# megatemp.net
KiCad netlist of a schematic drawn in EAGLE
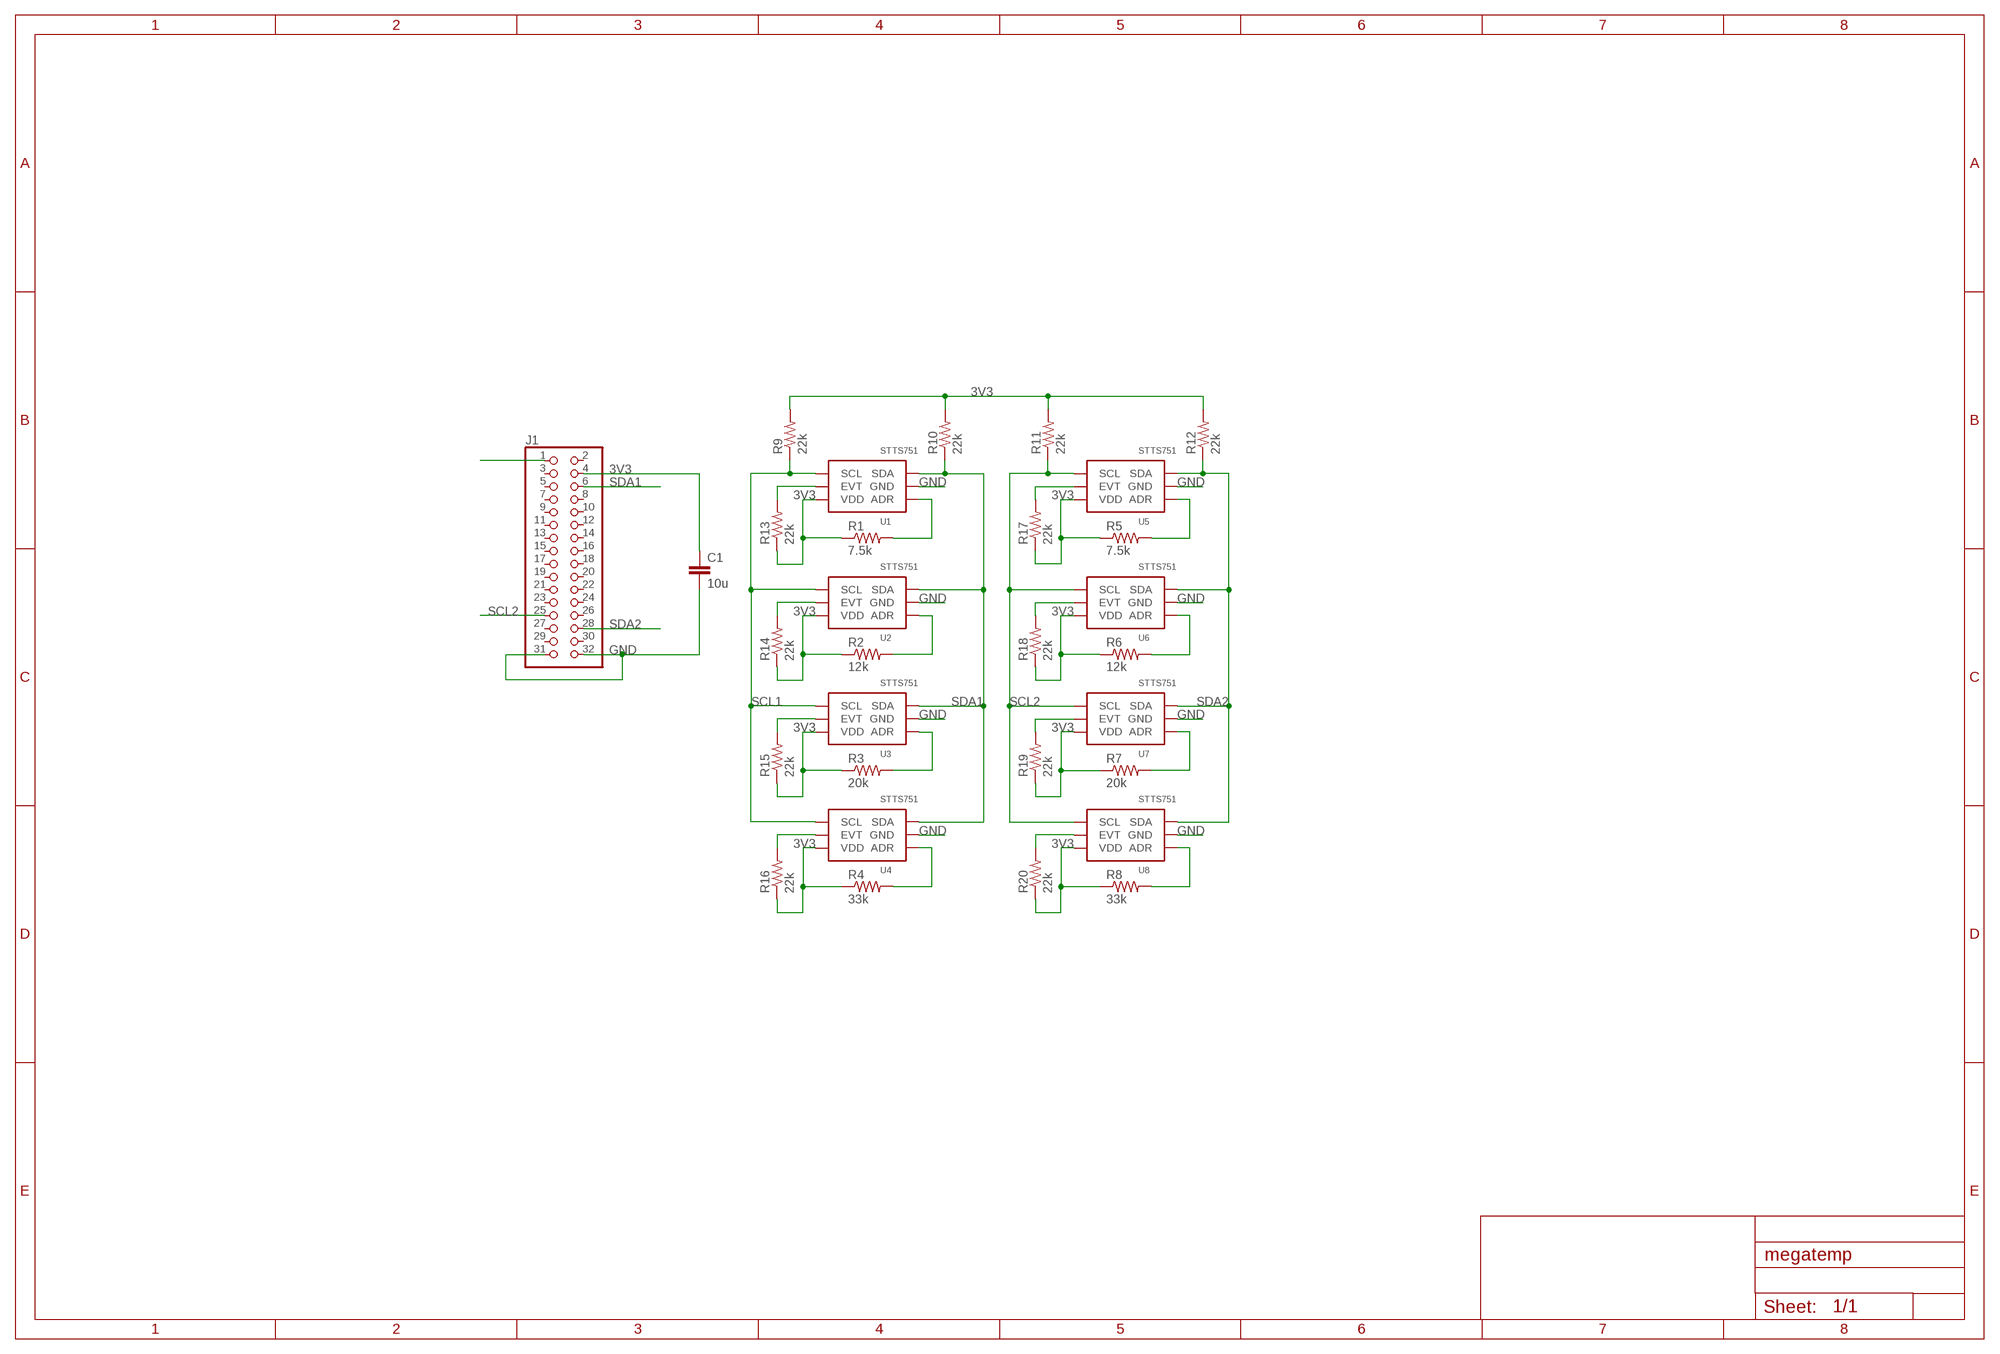
[diagram p0: schematic, sheet 1]

(export (version "E")
  (design (tool "Eeschema 10.0.6"))
  (components
    (comp (ref "C1")
      (value "10u")
      (footprint "eagle-import:C0805")
      (libsource (lib "eagle-import") (part "C-EUC0805"))
    )
    (comp (ref "J1")
      (value "PINHD-2X16")
      (footprint "eagle-import:2X16")
      (libsource (lib "eagle-import") (part "PINHD-2X16"))
    )
    (comp (ref "R1")
      (value "7.5k")
      (footprint "eagle-import:R0402")
      (libsource (lib "eagle-import") (part "R-US_R0402"))
    )
    (comp (ref "R2")
      (value "12k")
      (footprint "eagle-import:R0402")
      (libsource (lib "eagle-import") (part "R-US_R0402"))
    )
    (comp (ref "R3")
      (value "20k")
      (footprint "eagle-import:R0402")
      (libsource (lib "eagle-import") (part "R-US_R0402"))
    )
    (comp (ref "R4")
      (value "33k")
      (footprint "eagle-import:R0402")
      (libsource (lib "eagle-import") (part "R-US_R0402"))
    )
    (comp (ref "R5")
      (value "7.5k")
      (footprint "eagle-import:R0402")
      (libsource (lib "eagle-import") (part "R-US_R0402"))
    )
    (comp (ref "R6")
      (value "12k")
      (footprint "eagle-import:R0402")
      (libsource (lib "eagle-import") (part "R-US_R0402"))
    )
    (comp (ref "R7")
      (value "20k")
      (footprint "eagle-import:R0402")
      (libsource (lib "eagle-import") (part "R-US_R0402"))
    )
    (comp (ref "R8")
      (value "33k")
      (footprint "eagle-import:R0402")
      (libsource (lib "eagle-import") (part "R-US_R0402"))
    )
    (comp (ref "R9")
      (value "22k")
      (footprint "eagle-import:R0402")
      (libsource (lib "eagle-import") (part "R-US_R0402"))
    )
    (comp (ref "R10")
      (value "22k")
      (footprint "eagle-import:R0402")
      (libsource (lib "eagle-import") (part "R-US_R0402"))
    )
    (comp (ref "R11")
      (value "22k")
      (footprint "eagle-import:R0402")
      (libsource (lib "eagle-import") (part "R-US_R0402"))
    )
    (comp (ref "R12")
      (value "22k")
      (footprint "eagle-import:R0402")
      (libsource (lib "eagle-import") (part "R-US_R0402"))
    )
    (comp (ref "R13")
      (value "22k")
      (footprint "eagle-import:R0402")
      (libsource (lib "eagle-import") (part "R-US_R0402"))
    )
    (comp (ref "R14")
      (value "22k")
      (footprint "eagle-import:R0402")
      (libsource (lib "eagle-import") (part "R-US_R0402"))
    )
    (comp (ref "R15")
      (value "22k")
      (footprint "eagle-import:R0402")
      (libsource (lib "eagle-import") (part "R-US_R0402"))
    )
    (comp (ref "R16")
      (value "22k")
      (footprint "eagle-import:R0402")
      (libsource (lib "eagle-import") (part "R-US_R0402"))
    )
    (comp (ref "R17")
      (value "22k")
      (footprint "eagle-import:R0402")
      (libsource (lib "eagle-import") (part "R-US_R0402"))
    )
    (comp (ref "R18")
      (value "22k")
      (footprint "eagle-import:R0402")
      (libsource (lib "eagle-import") (part "R-US_R0402"))
    )
    (comp (ref "R19")
      (value "22k")
      (footprint "eagle-import:R0402")
      (libsource (lib "eagle-import") (part "R-US_R0402"))
    )
    (comp (ref "R20")
      (value "22k")
      (footprint "eagle-import:R0402")
      (libsource (lib "eagle-import") (part "R-US_R0402"))
    )
    (comp (ref "U1")
      (value "STTS751")
      (footprint "eagle-import:ST_UDFN-6L_2X2")
      (libsource (lib "eagle-import") (part "STTS751"))
    )
    (comp (ref "U2")
      (value "STTS751")
      (footprint "eagle-import:ST_UDFN-6L_2X2")
      (libsource (lib "eagle-import") (part "STTS751"))
    )
    (comp (ref "U3")
      (value "STTS751")
      (footprint "eagle-import:ST_UDFN-6L_2X2")
      (libsource (lib "eagle-import") (part "STTS751"))
    )
    (comp (ref "U4")
      (value "STTS751")
      (footprint "eagle-import:ST_UDFN-6L_2X2")
      (libsource (lib "eagle-import") (part "STTS751"))
    )
    (comp (ref "U5")
      (value "STTS751")
      (footprint "eagle-import:ST_UDFN-6L_2X2")
      (libsource (lib "eagle-import") (part "STTS751"))
    )
    (comp (ref "U6")
      (value "STTS751")
      (footprint "eagle-import:ST_UDFN-6L_2X2")
      (libsource (lib "eagle-import") (part "STTS751"))
    )
    (comp (ref "U7")
      (value "STTS751")
      (footprint "eagle-import:ST_UDFN-6L_2X2")
      (libsource (lib "eagle-import") (part "STTS751"))
    )
    (comp (ref "U8")
      (value "STTS751")
      (footprint "eagle-import:ST_UDFN-6L_2X2")
      (libsource (lib "eagle-import") (part "STTS751"))
    )
  )
  (nets
    (net (code "1") (name "/3V3") (class "Default")
      (node (ref "C1") (pin "1") (pinfunction "1_1") (pintype "passive"))
      (node (ref "J1") (pin "4") (pinfunction "4_4") (pintype "passive"))
      (node (ref "R1") (pin "1") (pinfunction "1_1") (pintype "passive"))
      (node (ref "R10") (pin "2") (pinfunction "2_2") (pintype "passive"))
      (node (ref "R11") (pin "2") (pinfunction "2_2") (pintype "passive"))
      (node (ref "R12") (pin "2") (pinfunction "2_2") (pintype "passive"))
      (node (ref "R13") (pin "1") (pinfunction "1_1") (pintype "passive"))
      (node (ref "R14") (pin "1") (pinfunction "1_1") (pintype "passive"))
      (node (ref "R15") (pin "1") (pinfunction "1_1") (pintype "passive"))
      (node (ref "R16") (pin "1") (pinfunction "1_1") (pintype "passive"))
      (node (ref "R17") (pin "1") (pinfunction "1_1") (pintype "passive"))
      (node (ref "R18") (pin "1") (pinfunction "1_1") (pintype "passive"))
      (node (ref "R19") (pin "1") (pinfunction "1_1") (pintype "passive"))
      (node (ref "R2") (pin "1") (pinfunction "1_1") (pintype "passive"))
      (node (ref "R20") (pin "1") (pinfunction "1_1") (pintype "passive"))
      (node (ref "R3") (pin "1") (pinfunction "1_1") (pintype "passive"))
      (node (ref "R4") (pin "1") (pinfunction "1_1") (pintype "passive"))
      (node (ref "R5") (pin "1") (pinfunction "1_1") (pintype "passive"))
      (node (ref "R6") (pin "1") (pinfunction "1_1") (pintype "passive"))
      (node (ref "R7") (pin "1") (pinfunction "1_1") (pintype "passive"))
      (node (ref "R8") (pin "1") (pinfunction "1_1") (pintype "passive"))
      (node (ref "R9") (pin "2") (pinfunction "2_2") (pintype "passive"))
      (node (ref "U1") (pin "3") (pinfunction "VDD_3") (pintype "bidirectional"))
      (node (ref "U2") (pin "3") (pinfunction "VDD_3") (pintype "bidirectional"))
      (node (ref "U3") (pin "3") (pinfunction "VDD_3") (pintype "bidirectional"))
      (node (ref "U4") (pin "3") (pinfunction "VDD_3") (pintype "bidirectional"))
      (node (ref "U5") (pin "3") (pinfunction "VDD_3") (pintype "bidirectional"))
      (node (ref "U6") (pin "3") (pinfunction "VDD_3") (pintype "bidirectional"))
      (node (ref "U7") (pin "3") (pinfunction "VDD_3") (pintype "bidirectional"))
      (node (ref "U8") (pin "3") (pinfunction "VDD_3") (pintype "bidirectional"))
    )
    (net (code "2") (name "/GND") (class "Default")
      (node (ref "C1") (pin "2") (pinfunction "2_2") (pintype "passive"))
      (node (ref "J1") (pin "31") (pinfunction "31_31") (pintype "passive"))
      (node (ref "J1") (pin "32") (pinfunction "32_32") (pintype "passive"))
      (node (ref "U1") (pin "5") (pinfunction "GND_5") (pintype "bidirectional"))
      (node (ref "U2") (pin "5") (pinfunction "GND_5") (pintype "bidirectional"))
      (node (ref "U3") (pin "5") (pinfunction "GND_5") (pintype "bidirectional"))
      (node (ref "U4") (pin "5") (pinfunction "GND_5") (pintype "bidirectional"))
      (node (ref "U5") (pin "5") (pinfunction "GND_5") (pintype "bidirectional"))
      (node (ref "U6") (pin "5") (pinfunction "GND_5") (pintype "bidirectional"))
      (node (ref "U7") (pin "5") (pinfunction "GND_5") (pintype "bidirectional"))
      (node (ref "U8") (pin "5") (pinfunction "GND_5") (pintype "bidirectional"))
    )
    (net (code "3") (name "/SCL1") (class "Default")
      (node (ref "J1") (pin "1") (pinfunction "1_1") (pintype "passive"))
      (node (ref "R9") (pin "1") (pinfunction "1_1") (pintype "passive"))
      (node (ref "U1") (pin "1") (pinfunction "SCL_1") (pintype "bidirectional"))
      (node (ref "U2") (pin "1") (pinfunction "SCL_1") (pintype "bidirectional"))
      (node (ref "U3") (pin "1") (pinfunction "SCL_1") (pintype "bidirectional"))
      (node (ref "U4") (pin "1") (pinfunction "SCL_1") (pintype "bidirectional"))
    )
    (net (code "4") (name "/SCL2") (class "Default")
      (node (ref "J1") (pin "25") (pinfunction "25_25") (pintype "passive"))
      (node (ref "R11") (pin "1") (pinfunction "1_1") (pintype "passive"))
      (node (ref "U5") (pin "1") (pinfunction "SCL_1") (pintype "bidirectional"))
      (node (ref "U6") (pin "1") (pinfunction "SCL_1") (pintype "bidirectional"))
      (node (ref "U7") (pin "1") (pinfunction "SCL_1") (pintype "bidirectional"))
      (node (ref "U8") (pin "1") (pinfunction "SCL_1") (pintype "bidirectional"))
    )
    (net (code "5") (name "/SDA1") (class "Default")
      (node (ref "J1") (pin "6") (pinfunction "6_6") (pintype "passive"))
      (node (ref "R10") (pin "1") (pinfunction "1_1") (pintype "passive"))
      (node (ref "U1") (pin "6") (pinfunction "SDA_6") (pintype "bidirectional"))
      (node (ref "U2") (pin "6") (pinfunction "SDA_6") (pintype "bidirectional"))
      (node (ref "U3") (pin "6") (pinfunction "SDA_6") (pintype "bidirectional"))
      (node (ref "U4") (pin "6") (pinfunction "SDA_6") (pintype "bidirectional"))
    )
    (net (code "6") (name "/SDA2") (class "Default")
      (node (ref "J1") (pin "28") (pinfunction "28_28") (pintype "passive"))
      (node (ref "R12") (pin "1") (pinfunction "1_1") (pintype "passive"))
      (node (ref "U5") (pin "6") (pinfunction "SDA_6") (pintype "bidirectional"))
      (node (ref "U6") (pin "6") (pinfunction "SDA_6") (pintype "bidirectional"))
      (node (ref "U7") (pin "6") (pinfunction "SDA_6") (pintype "bidirectional"))
      (node (ref "U8") (pin "6") (pinfunction "SDA_6") (pintype "bidirectional"))
    )
    (net (code "7") (name "Net-(U1-ADR)") (class "Default")
      (node (ref "R1") (pin "2") (pinfunction "2_2") (pintype "passive"))
      (node (ref "U1") (pin "4") (pinfunction "ADR_4") (pintype "bidirectional"))
    )
    (net (code "8") (name "Net-(U1-EVT)") (class "Default")
      (node (ref "R13") (pin "2") (pinfunction "2_2") (pintype "passive"))
      (node (ref "U1") (pin "2") (pinfunction "EVT_2") (pintype "bidirectional"))
    )
    (net (code "9") (name "Net-(U2-ADR)") (class "Default")
      (node (ref "R2") (pin "2") (pinfunction "2_2") (pintype "passive"))
      (node (ref "U2") (pin "4") (pinfunction "ADR_4") (pintype "bidirectional"))
    )
    (net (code "10") (name "Net-(U2-EVT)") (class "Default")
      (node (ref "R14") (pin "2") (pinfunction "2_2") (pintype "passive"))
      (node (ref "U2") (pin "2") (pinfunction "EVT_2") (pintype "bidirectional"))
    )
    (net (code "11") (name "Net-(U3-ADR)") (class "Default")
      (node (ref "R3") (pin "2") (pinfunction "2_2") (pintype "passive"))
      (node (ref "U3") (pin "4") (pinfunction "ADR_4") (pintype "bidirectional"))
    )
    (net (code "12") (name "Net-(U3-EVT)") (class "Default")
      (node (ref "R15") (pin "2") (pinfunction "2_2") (pintype "passive"))
      (node (ref "U3") (pin "2") (pinfunction "EVT_2") (pintype "bidirectional"))
    )
    (net (code "13") (name "Net-(U4-ADR)") (class "Default")
      (node (ref "R4") (pin "2") (pinfunction "2_2") (pintype "passive"))
      (node (ref "U4") (pin "4") (pinfunction "ADR_4") (pintype "bidirectional"))
    )
    (net (code "14") (name "Net-(U4-EVT)") (class "Default")
      (node (ref "R16") (pin "2") (pinfunction "2_2") (pintype "passive"))
      (node (ref "U4") (pin "2") (pinfunction "EVT_2") (pintype "bidirectional"))
    )
    (net (code "15") (name "Net-(U5-ADR)") (class "Default")
      (node (ref "R5") (pin "2") (pinfunction "2_2") (pintype "passive"))
      (node (ref "U5") (pin "4") (pinfunction "ADR_4") (pintype "bidirectional"))
    )
    (net (code "16") (name "Net-(U5-EVT)") (class "Default")
      (node (ref "R17") (pin "2") (pinfunction "2_2") (pintype "passive"))
      (node (ref "U5") (pin "2") (pinfunction "EVT_2") (pintype "bidirectional"))
    )
    (net (code "17") (name "Net-(U6-ADR)") (class "Default")
      (node (ref "R6") (pin "2") (pinfunction "2_2") (pintype "passive"))
      (node (ref "U6") (pin "4") (pinfunction "ADR_4") (pintype "bidirectional"))
    )
    (net (code "18") (name "Net-(U6-EVT)") (class "Default")
      (node (ref "R18") (pin "2") (pinfunction "2_2") (pintype "passive"))
      (node (ref "U6") (pin "2") (pinfunction "EVT_2") (pintype "bidirectional"))
    )
    (net (code "19") (name "Net-(U7-ADR)") (class "Default")
      (node (ref "R7") (pin "2") (pinfunction "2_2") (pintype "passive"))
      (node (ref "U7") (pin "4") (pinfunction "ADR_4") (pintype "bidirectional"))
    )
    (net (code "20") (name "Net-(U7-EVT)") (class "Default")
      (node (ref "R19") (pin "2") (pinfunction "2_2") (pintype "passive"))
      (node (ref "U7") (pin "2") (pinfunction "EVT_2") (pintype "bidirectional"))
    )
    (net (code "21") (name "Net-(U8-ADR)") (class "Default")
      (node (ref "R8") (pin "2") (pinfunction "2_2") (pintype "passive"))
      (node (ref "U8") (pin "4") (pinfunction "ADR_4") (pintype "bidirectional"))
    )
    (net (code "22") (name "Net-(U8-EVT)") (class "Default")
      (node (ref "R20") (pin "2") (pinfunction "2_2") (pintype "passive"))
      (node (ref "U8") (pin "2") (pinfunction "EVT_2") (pintype "bidirectional"))
    )
    (net (code "23") (name "unconnected-(J1-Pad2)") (class "Default")
      (node (ref "J1") (pin "2") (pinfunction "2_2") (pintype "passive"))
    )
    (net (code "24") (name "unconnected-(J1-Pad3)") (class "Default")
      (node (ref "J1") (pin "3") (pinfunction "3_3") (pintype "passive"))
    )
    (net (code "25") (name "unconnected-(J1-Pad5)") (class "Default")
      (node (ref "J1") (pin "5") (pinfunction "5_5") (pintype "passive"))
    )
    (net (code "26") (name "unconnected-(J1-Pad7)") (class "Default")
      (node (ref "J1") (pin "7") (pinfunction "7_7") (pintype "passive"))
    )
    (net (code "27") (name "unconnected-(J1-Pad8)") (class "Default")
      (node (ref "J1") (pin "8") (pinfunction "8_8") (pintype "passive"))
    )
    (net (code "28") (name "unconnected-(J1-Pad9)") (class "Default")
      (node (ref "J1") (pin "9") (pinfunction "9_9") (pintype "passive"))
    )
    (net (code "29") (name "unconnected-(J1-Pad10)") (class "Default")
      (node (ref "J1") (pin "10") (pinfunction "10_10") (pintype "passive"))
    )
    (net (code "30") (name "unconnected-(J1-Pad11)") (class "Default")
      (node (ref "J1") (pin "11") (pinfunction "11_11") (pintype "passive"))
    )
    (net (code "31") (name "unconnected-(J1-Pad12)") (class "Default")
      (node (ref "J1") (pin "12") (pinfunction "12_12") (pintype "passive"))
    )
    (net (code "32") (name "unconnected-(J1-Pad13)") (class "Default")
      (node (ref "J1") (pin "13") (pinfunction "13_13") (pintype "passive"))
    )
    (net (code "33") (name "unconnected-(J1-Pad14)") (class "Default")
      (node (ref "J1") (pin "14") (pinfunction "14_14") (pintype "passive"))
    )
    (net (code "34") (name "unconnected-(J1-Pad15)") (class "Default")
      (node (ref "J1") (pin "15") (pinfunction "15_15") (pintype "passive"))
    )
    (net (code "35") (name "unconnected-(J1-Pad16)") (class "Default")
      (node (ref "J1") (pin "16") (pinfunction "16_16") (pintype "passive"))
    )
    (net (code "36") (name "unconnected-(J1-Pad17)") (class "Default")
      (node (ref "J1") (pin "17") (pinfunction "17_17") (pintype "passive"))
    )
    (net (code "37") (name "unconnected-(J1-Pad18)") (class "Default")
      (node (ref "J1") (pin "18") (pinfunction "18_18") (pintype "passive"))
    )
    (net (code "38") (name "unconnected-(J1-Pad19)") (class "Default")
      (node (ref "J1") (pin "19") (pinfunction "19_19") (pintype "passive"))
    )
    (net (code "39") (name "unconnected-(J1-Pad20)") (class "Default")
      (node (ref "J1") (pin "20") (pinfunction "20_20") (pintype "passive"))
    )
    (net (code "40") (name "unconnected-(J1-Pad21)") (class "Default")
      (node (ref "J1") (pin "21") (pinfunction "21_21") (pintype "passive"))
    )
    (net (code "41") (name "unconnected-(J1-Pad22)") (class "Default")
      (node (ref "J1") (pin "22") (pinfunction "22_22") (pintype "passive"))
    )
    (net (code "42") (name "unconnected-(J1-Pad23)") (class "Default")
      (node (ref "J1") (pin "23") (pinfunction "23_23") (pintype "passive"))
    )
    (net (code "43") (name "unconnected-(J1-Pad24)") (class "Default")
      (node (ref "J1") (pin "24") (pinfunction "24_24") (pintype "passive"))
    )
    (net (code "44") (name "unconnected-(J1-Pad26)") (class "Default")
      (node (ref "J1") (pin "26") (pinfunction "26_26") (pintype "passive"))
    )
    (net (code "45") (name "unconnected-(J1-Pad27)") (class "Default")
      (node (ref "J1") (pin "27") (pinfunction "27_27") (pintype "passive"))
    )
    (net (code "46") (name "unconnected-(J1-Pad29)") (class "Default")
      (node (ref "J1") (pin "29") (pinfunction "29_29") (pintype "passive"))
    )
    (net (code "47") (name "unconnected-(J1-Pad30)") (class "Default")
      (node (ref "J1") (pin "30") (pinfunction "30_30") (pintype "passive"))
    )
  )
)
